# 15_PM8916_CHARGING_GPIO.net
KiCad netlist of a schematic drawn in Altium Designer
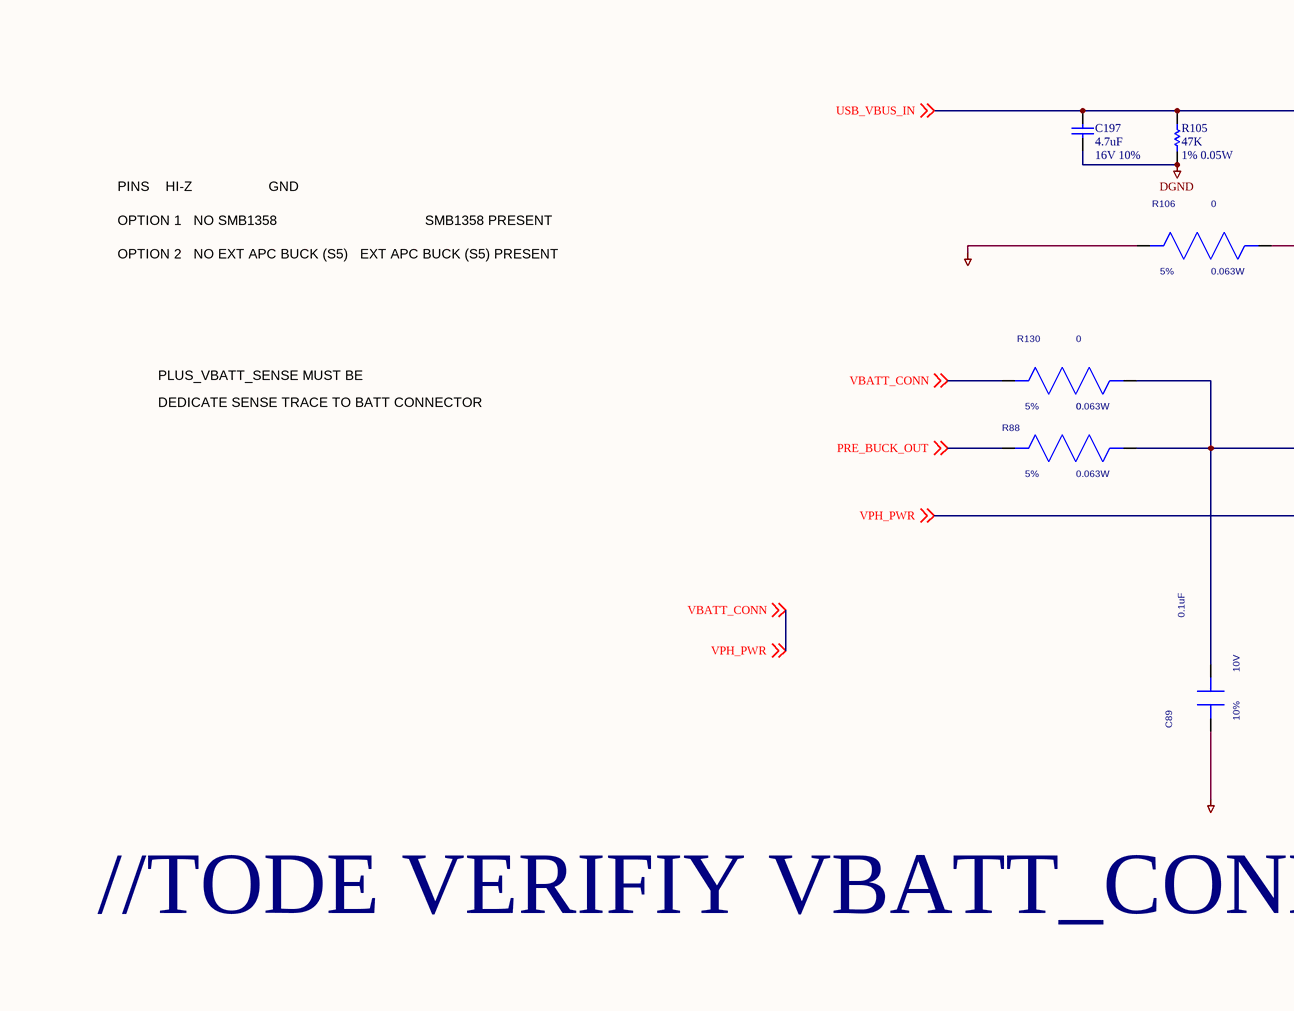
[diagram p0: 15 PM8916_CHARGING GPIO.SchDoc, top left]
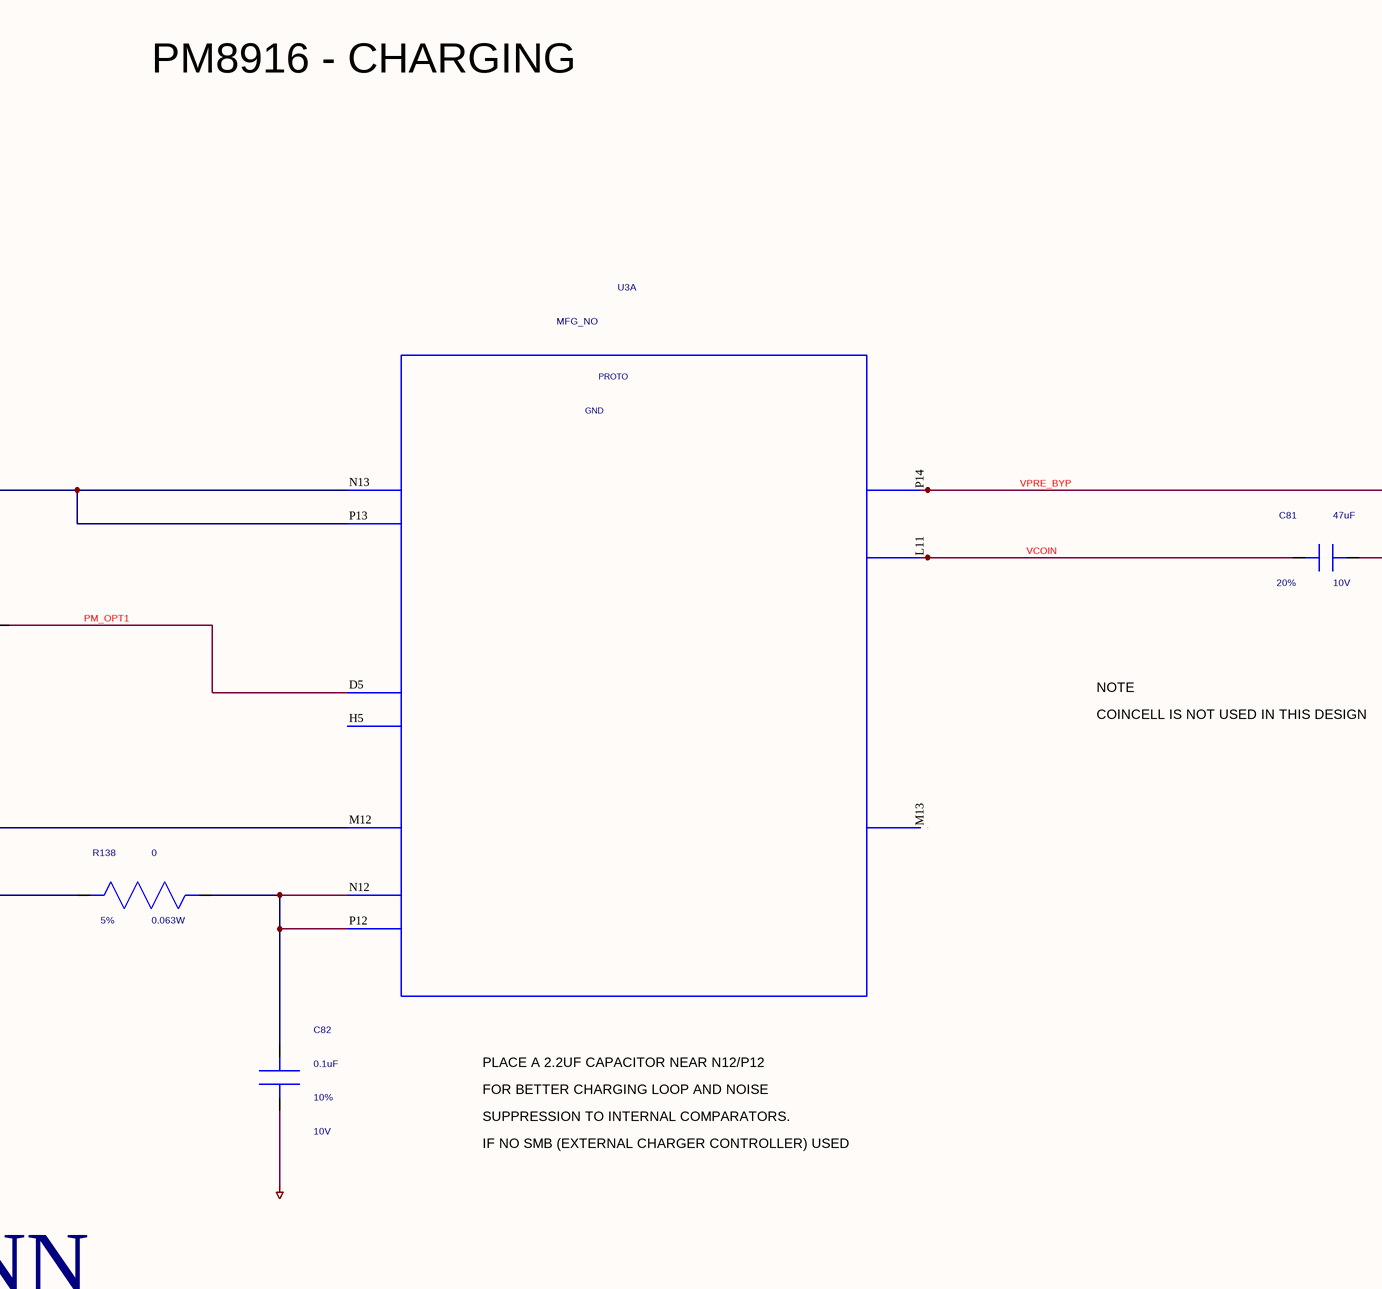
[diagram p1: 15 PM8916_CHARGING GPIO.SchDoc, top middle]
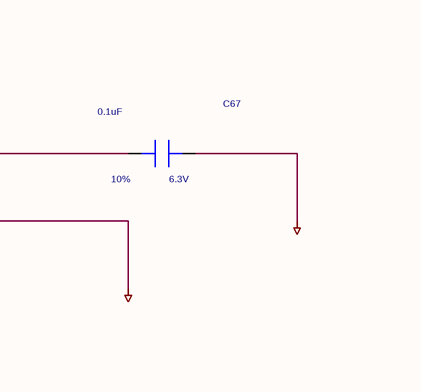
[diagram p2: 15 PM8916_CHARGING GPIO.SchDoc, top right]
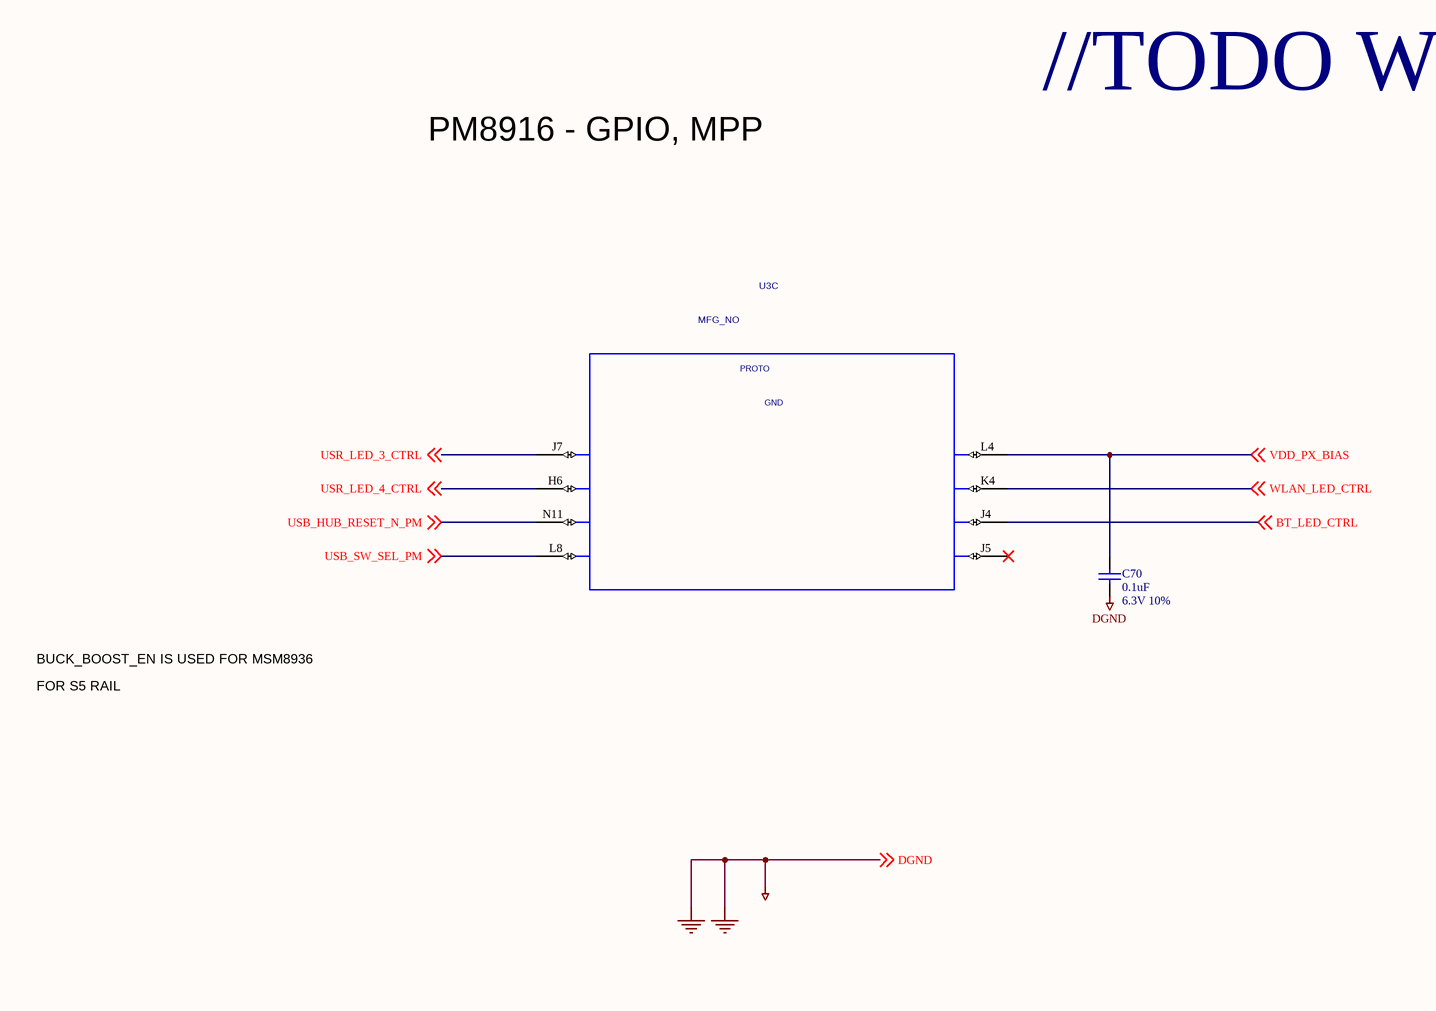
[diagram p3: 15 PM8916_CHARGING GPIO.SchDoc, bottom left]
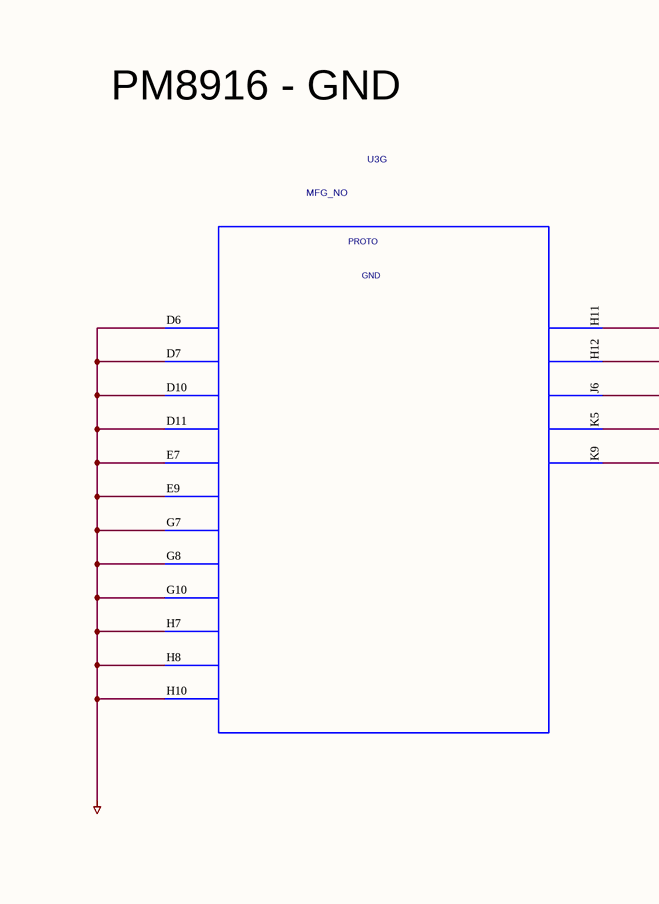
[diagram p4: 15 PM8916_CHARGING GPIO.SchDoc, bottom middle]
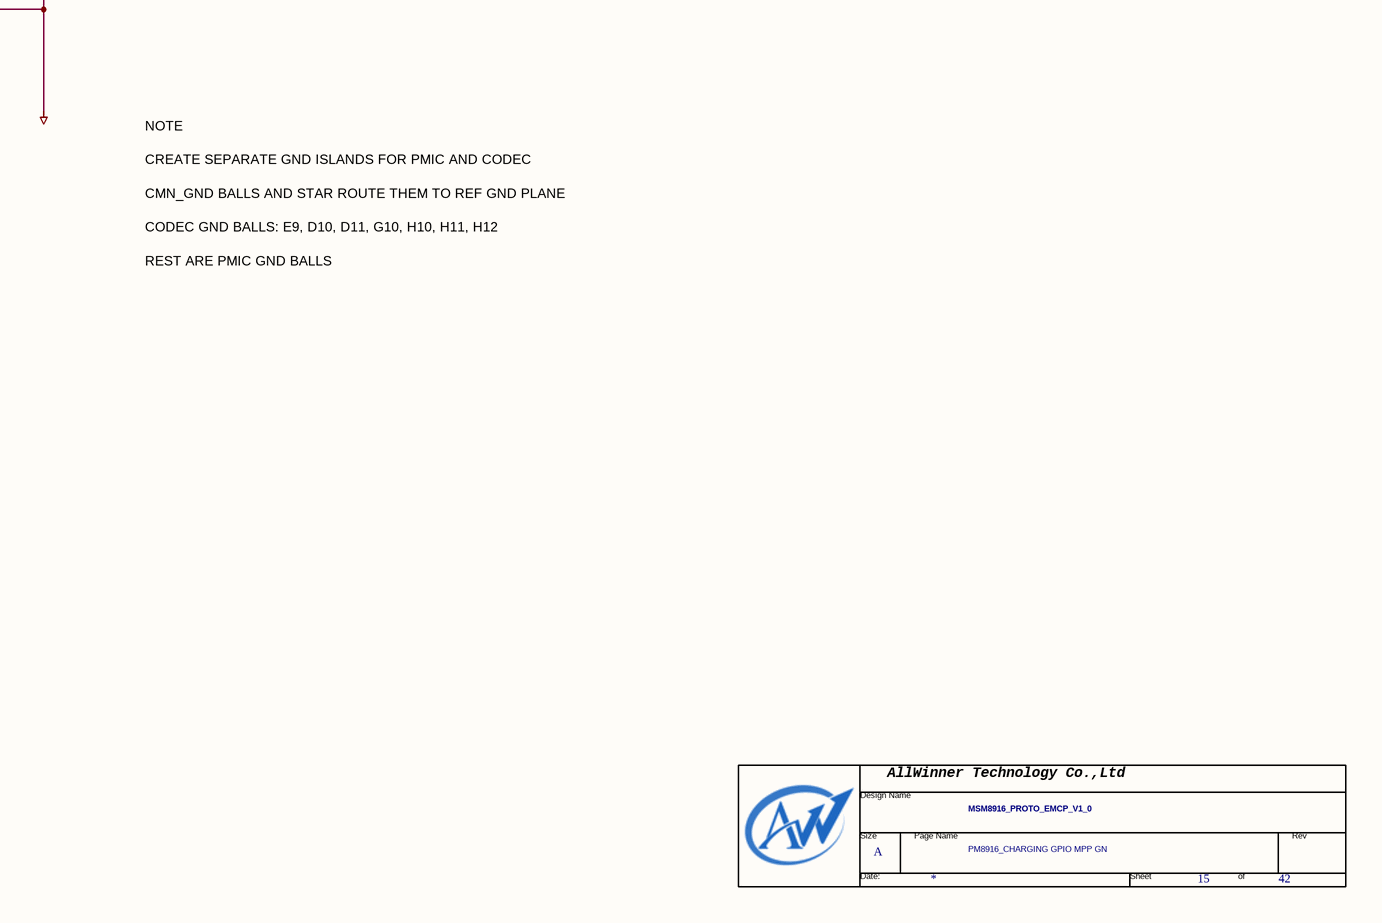
[diagram p5: 15 PM8916_CHARGING GPIO.SchDoc, bottom right]

(export (version "E")
  (design (tool "Eeschema 10.0.6"))
  (components
    (comp (ref "*")
      (value "TitleBlock0-AW")
      (fields
        (field (name "PAGE COUNT") "42")
        (field (name "PAGE NUMBER") "15")
        (field (name "PAGE SIZE") "A")
        (field (name "TITLE") "MSM8916_PROTO_EMCP_V1_0")
        (field (name "DOC") "PM8916_CHARGING GPIO MPP GN")
      )
      (libsource (lib "*") (part "TitleBlock0-AW"))
    )
    (comp (ref "C67")
      (value "0.1uF")
      (fields
        (field (name "VOLT") "10%")
        (field (name "TOLERANCE") "6.3V")
        (field (name "PART_NUMBER") "MCN_NO")
      )
      (libsource (lib "MSM8916_DRAM_PMIC_REF_Library") (part "CAP#1"))
    )
    (comp (ref "C70")
      (value "0.1uF")
      (footprint "RAD-0.3")
      (description "Capacitor")
      (fields (field (name "ALTIUM_VALUE") "6.3V 10%") (field (name "PUBLISHER") "Altium Limited"))
      (libsource (lib "Miscellaneous Devices") (part "Cap"))
    )
    (comp (ref "C81")
      (value "47uF")
      (fields
        (field (name "VOLT") "10V")
        (field (name "TOLERANCE") "20%")
        (field (name "PART_NUMBER") "MCN_NO")
      )
      (libsource (lib "MSM8916_DRAM_PMIC_REF_Library") (part "CAP#1"))
    )
    (comp (ref "C82")
      (value "0.1uF")
      (fields
        (field (name "VOLT") "10V")
        (field (name "TOLERANCE") "10%")
        (field (name "PART_NUMBER") "MCN_NO")
      )
      (libsource (lib "MSM8916_DRAM_PMIC_REF_Library") (part "CAP"))
    )
    (comp (ref "C89")
      (value "0.1uF")
      (fields
        (field (name "VOLT") "10V")
        (field (name "TOLERANCE") "10%")
        (field (name "PART_NUMBER") "MCN_NO")
      )
      (libsource (lib "MSM8916_DRAM_PMIC_REF_Library") (part "CAP#1"))
    )
    (comp (ref "C197")
      (value "4.7uF")
      (footprint "RAD-0.3")
      (description "Capacitor")
      (fields (field (name "ALTIUM_VALUE") "16V 10%") (field (name "PUBLISHER") "Altium Limited"))
      (libsource (lib "Miscellaneous Devices") (part "Cap"))
    )
    (comp (ref "R88")
      (value "0")
      (fields
        (field (name "TOLERANCE") "5%")
        (field (name "POWER") "0.063W")
        (field (name "PART_NUMBER") "MCN_NO")
      )
      (libsource (lib "MSM8916_DRAM_PMIC_REF_Library") (part "RESISTOR_Dup3"))
    )
    (comp (ref "R105")
      (value "47K")
      (footprint "AXIAL-0.3")
      (description "Resistor")
      (fields (field (name "ALTIUM_VALUE") "1% 0.05W") (field (name "PUBLISHER") "Altium Limited"))
      (libsource (lib "Miscellaneous Devices") (part "Res1"))
    )
    (comp (ref "R106")
      (value "0")
      (fields
        (field (name "TOLERANCE") "5%")
        (field (name "POWER") "0.063W")
        (field (name "PART_NUMBER") "MCN_NO")
      )
      (libsource (lib "MSM8916_DRAM_PMIC_REF_Library") (part "RESISTOR_Dup3"))
    )
    (comp (ref "R130")
      (value "0")
      (fields
        (field (name "TOLERANCE") "5%")
        (field (name "POWER") "0.063W")
        (field (name "PART_NUMBER") "MCN_NO")
      )
      (libsource (lib "MSM8916_DRAM_PMIC_REF_Library") (part "RESISTOR_Dup3"))
    )
    (comp (ref "R138")
      (value "0")
      (fields
        (field (name "TOLERANCE") "5%")
        (field (name "POWER") "0.063W")
        (field (name "PART_NUMBER") "MCN_NO")
      )
      (libsource (lib "MSM8916_DRAM_PMIC_REF_Library") (part "RESISTOR_Dup3"))
    )
    (comp (ref "U3")
      (value "ASIC_PM8916")
      (footprint "PM-8916-0-176NSP-TR-00-0")
      (fields
        (field (name "SYMNAME") "GND")
        (field (name "PART_NUMBER") "MCN_NO")
        (field (name "PART_ID") "MFG_NO")
        (field (name "BLOCKID") "PROTO")
      )
      (libsource (lib "MSM8916_DRAM_PMIC_REF_Library") (part "ASIC_PM8916"))
    )
  )
  (nets
    (net (code "1") (name "/PM_OPT1") (class "Default")
      (node (ref "R106") (pin "2") (pinfunction "NEG_2") (pintype "bidirectional"))
      (node (ref "U3") (pin "D5") (pinfunction "OPTION1_D5") (pintype "bidirectional"))
    )
    (net (code "2") (name "/VCOIN") (class "Default")
      (node (ref "C81") (pin "1") (pinfunction "POS_1") (pintype "bidirectional"))
      (node (ref "U3") (pin "L11") (pinfunction "VCOIN_L11") (pintype "bidirectional"))
    )
    (net (code "3") (name "/VPRE_BYP") (class "Default")
      (node (ref "C67") (pin "2") (pinfunction "NEG_2") (pintype "bidirectional"))
      (node (ref "U3") (pin "P14") (pinfunction "VPRE_BYP_P14") (pintype "bidirectional"))
    )
    (net (code "4") (name "BT_LED_CTRL") (class "Default")
      (node (ref "U3") (pin "J4") (pinfunction "MPP3_J4") (pintype "bidirectional"))
    )
    (net (code "5") (name "DGND") (class "Default")
      (node (ref "C197") (pin "1") (pinfunction "1_1") (pintype "passive"))
      (node (ref "C67") (pin "1") (pinfunction "POS_1") (pintype "bidirectional"))
      (node (ref "C70") (pin "1") (pinfunction "1_1") (pintype "passive"))
      (node (ref "C81") (pin "2") (pinfunction "NEG_2") (pintype "bidirectional"))
      (node (ref "C82") (pin "2") (pinfunction "NEG_2") (pintype "bidirectional"))
      (node (ref "C89") (pin "1") (pinfunction "POS_1") (pintype "bidirectional"))
      (node (ref "R105") (pin "1") (pinfunction "1_1") (pintype "passive"))
      (node (ref "R106") (pin "1") (pinfunction "POS_1") (pintype "bidirectional"))
      (node (ref "U3") (pin "D10") (pinfunction "CMN_GND_3_D10") (pintype "input"))
      (node (ref "U3") (pin "D11") (pinfunction "CMN_GND_4_D11") (pintype "input"))
      (node (ref "U3") (pin "D6") (pinfunction "CMN_GND_1_D6") (pintype "input"))
      (node (ref "U3") (pin "D7") (pinfunction "CMN_GND_2_D7") (pintype "input"))
      (node (ref "U3") (pin "E7") (pinfunction "CMN_GND_5_E7") (pintype "input"))
      (node (ref "U3") (pin "E9") (pinfunction "CMN_GND_6_E9") (pintype "input"))
      (node (ref "U3") (pin "G10") (pinfunction "CMN_GND_9_G10") (pintype "input"))
      (node (ref "U3") (pin "G7") (pinfunction "CMN_GND_7_G7") (pintype "input"))
      (node (ref "U3") (pin "G8") (pinfunction "CMN_GND_8_G8") (pintype "input"))
      (node (ref "U3") (pin "H10") (pinfunction "CMN_GND_12_H10") (pintype "input"))
      (node (ref "U3") (pin "H11") (pinfunction "CMN_GND_13_H11") (pintype "input"))
      (node (ref "U3") (pin "H12") (pinfunction "CMN_GND_14_H12") (pintype "input"))
      (node (ref "U3") (pin "H7") (pinfunction "CMN_GND_10_H7") (pintype "input"))
      (node (ref "U3") (pin "H8") (pinfunction "CMN_GND_11_H8") (pintype "input"))
      (node (ref "U3") (pin "J6") (pinfunction "CMN_GND_15_J6") (pintype "input"))
      (node (ref "U3") (pin "K5") (pinfunction "CMN_GND_16_K5") (pintype "input"))
      (node (ref "U3") (pin "K9") (pinfunction "CMN_GND_17_K9") (pintype "input"))
    )
    (net (code "6") (name "Net-(C82-POS)") (class "Default")
      (node (ref "C82") (pin "1") (pinfunction "POS_1") (pintype "bidirectional"))
      (node (ref "R138") (pin "2") (pinfunction "NEG_2") (pintype "bidirectional"))
      (node (ref "U3") (pin "N12") (pinfunction "VBAT1_N12") (pintype "bidirectional"))
      (node (ref "U3") (pin "P12") (pinfunction "VBAT2_P12") (pintype "bidirectional"))
    )
    (net (code "7") (name "Net-(C89-NEG)") (class "Default")
      (node (ref "C89") (pin "2") (pinfunction "NEG_2") (pintype "bidirectional"))
      (node (ref "R130") (pin "2") (pinfunction "NEG_2") (pintype "bidirectional"))
      (node (ref "R88") (pin "2") (pinfunction "NEG_2") (pintype "bidirectional"))
      (node (ref "U3") (pin "M12") (pinfunction "VBAT_SNS_M12") (pintype "bidirectional"))
    )
    (net (code "8") (name "PRE_BUCK_OUT") (class "Default")
      (node (ref "R88") (pin "1") (pinfunction "POS_1") (pintype "bidirectional"))
    )
    (net (code "9") (name "USB_HUB_RESET_N_PM") (class "Default")
      (node (ref "U3") (pin "N11") (pinfunction "GPIO3_N11") (pintype "bidirectional"))
    )
    (net (code "10") (name "USB_SW_SEL_PM") (class "Default")
      (node (ref "U3") (pin "L8") (pinfunction "GPIO4_L8") (pintype "bidirectional"))
    )
    (net (code "11") (name "USB_VBUS_IN") (class "Default")
      (node (ref "C197") (pin "2") (pinfunction "2_2") (pintype "passive"))
      (node (ref "R105") (pin "2") (pinfunction "2_2") (pintype "passive"))
      (node (ref "U3") (pin "N13") (pinfunction "USB_IN1_N13") (pintype "bidirectional"))
      (node (ref "U3") (pin "P13") (pinfunction "USB_IN2_P13") (pintype "bidirectional"))
    )
    (net (code "12") (name "USR_LED_3_CTRL") (class "Default")
      (node (ref "U3") (pin "J7") (pinfunction "GPIO1_J7") (pintype "bidirectional"))
    )
    (net (code "13") (name "USR_LED_4_CTRL") (class "Default")
      (node (ref "U3") (pin "H6") (pinfunction "GPIO2_H6") (pintype "bidirectional"))
    )
    (net (code "14") (name "VBATT_CONN") (class "Default")
      (node (ref "R130") (pin "1") (pinfunction "POS_1") (pintype "bidirectional"))
      (node (ref "R138") (pin "1") (pinfunction "POS_1") (pintype "bidirectional"))
    )
    (net (code "15") (name "VDD_PX_BIAS") (class "Default")
      (node (ref "C70") (pin "2") (pinfunction "2_2") (pintype "passive"))
      (node (ref "U3") (pin "L4") (pinfunction "MPP1_L4") (pintype "bidirectional"))
    )
    (net (code "16") (name "WLAN_LED_CTRL") (class "Default")
      (node (ref "U3") (pin "K4") (pinfunction "MPP2_K4") (pintype "bidirectional"))
    )
    (net (code "17") (name "unconnected-(U3A-CHG_LED_SINK-PadM13)") (class "Default")
      (node (ref "U3") (pin "M13") (pinfunction "CHG_LED_SINK_M13") (pintype "bidirectional"))
    )
    (net (code "18") (name "unconnected-(U3A-OPTION2-PadH5)") (class "Default")
      (node (ref "U3") (pin "H5") (pinfunction "OPTION2_H5") (pintype "bidirectional"))
    )
    (net (code "19") (name "unconnected-(U3C-MPP4-PadJ5)") (class "Default")
      (node (ref "U3") (pin "J5") (pinfunction "MPP4_J5") (pintype "bidirectional+no_connect"))
    )
  )
)
